# Sch.net
KiCad netlist of a schematic drawn in Altium Designer
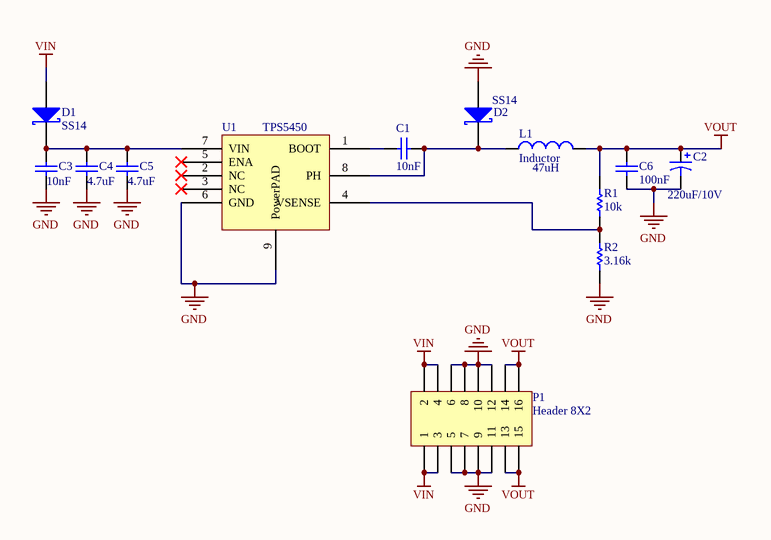
[diagram p0: Sch.SchDoc]

(export (version "E")
  (design (tool "Eeschema 10.0.6"))
  (components
    (comp (ref "C1")
      (value "10nF")
      (footprint "CAP1608(0603)")
      (description "Capacitor")
      (fields (field (name "PUBLISHER") "Altium Limited"))
      (libsource (lib "Miscellaneous Devices") (part "Cap"))
    )
    (comp (ref "C2")
      (value "220uF/10V")
      (footprint "CAP 2.5*6.3*7")
      (description "Polarized Capacitor (Radial)")
      (fields (field (name "PUBLISHER") "Altium Limited"))
      (libsource (lib "Miscellaneous Devices") (part "Cap Pol1"))
    )
    (comp (ref "C3")
      (value "10nF")
      (footprint "CAP1608(0603)")
      (description "Capacitor")
      (fields (field (name "PUBLISHER") "Altium Limited"))
      (libsource (lib "Miscellaneous Devices") (part "Cap"))
    )
    (comp (ref "C4")
      (value "4.7uF")
      (footprint "CAPC2012L")
      (description "Capacitor")
      (fields (field (name "PUBLISHER") "Altium Limited"))
      (libsource (lib "Miscellaneous Devices") (part "Cap"))
    )
    (comp (ref "C5")
      (value "4.7uF")
      (footprint "CAPC2012L")
      (description "Capacitor")
      (fields (field (name "PUBLISHER") "Altium Limited"))
      (libsource (lib "Miscellaneous Devices") (part "Cap"))
    )
    (comp (ref "C6")
      (value "100nF")
      (footprint "CAP1608(0603)")
      (description "Capacitor")
      (fields (field (name "PUBLISHER") "Altium Limited"))
      (libsource (lib "Miscellaneous Devices") (part "Cap"))
    )
    (comp (ref "D1")
      (value "SS14")
      (footprint "DIODE_SMA")
      (description "Schottky Diode")
      (fields (field (name "PUBLISHER") "Altium Limited"))
      (libsource (lib "Miscellaneous Devices") (part "D Schottky"))
    )
    (comp (ref "D2")
      (value "SS14")
      (footprint "DIODE_SMA")
      (description "Schottky Diode")
      (fields (field (name "PUBLISHER") "Altium Limited"))
      (libsource (lib "Miscellaneous Devices") (part "D Schottky"))
    )
    (comp (ref "L1")
      (value "Inductor")
      (footprint "CD43")
      (fields (field (name "ALTIUM_VALUE") "47uH") (field (name "PUBLISHER") "Altium Limited"))
      (libsource (lib "Miscellaneous Devices") (part "Inductor"))
    )
    (comp (ref "P1")
      (value "Header 8X2")
      (footprint "HDR2X8")
      (description "Header, 8-Pin, Dual row")
      (fields (field (name "PUBLISHER") "Altium Limited"))
      (libsource (lib "Miscellaneous Connectors") (part "Header 8X2"))
    )
    (comp (ref "R1")
      (value "10k")
      (footprint "RES1608(0603)")
      (description "Resistor")
      (fields (field (name "PUBLISHER") "Altium Limited"))
      (libsource (lib "Miscellaneous Devices") (part "Res1"))
    )
    (comp (ref "R2")
      (value "3.16k")
      (footprint "RES1608(0603)")
      (description "Resistor")
      (fields (field (name "PUBLISHER") "Altium Limited"))
      (libsource (lib "Miscellaneous Devices") (part "Res1"))
    )
    (comp (ref "U1") (value "TPS5450") (footprint "TPS5450") (libsource (lib "MySchlib") (part "TPS5450")))
  )
  (nets
    (net (code "1") (name "GND") (class "Default")
      (node (ref "C2") (pin "2") (pinfunction "2_2") (pintype "passive"))
      (node (ref "C3") (pin "2") (pinfunction "2_2") (pintype "passive"))
      (node (ref "C4") (pin "2") (pinfunction "2_2") (pintype "passive"))
      (node (ref "C5") (pin "2") (pinfunction "2_2") (pintype "passive"))
      (node (ref "C6") (pin "2") (pinfunction "2_2") (pintype "passive"))
      (node (ref "D2") (pin "1") (pinfunction "A_1") (pintype "passive"))
      (node (ref "P1") (pin "10") (pinfunction "10_10") (pintype "passive"))
      (node (ref "P1") (pin "11") (pinfunction "11_11") (pintype "passive"))
      (node (ref "P1") (pin "12") (pinfunction "12_12") (pintype "passive"))
      (node (ref "P1") (pin "5") (pinfunction "5_5") (pintype "passive"))
      (node (ref "P1") (pin "6") (pinfunction "6_6") (pintype "passive"))
      (node (ref "P1") (pin "7") (pinfunction "7_7") (pintype "passive"))
      (node (ref "P1") (pin "8") (pinfunction "8_8") (pintype "passive"))
      (node (ref "P1") (pin "9") (pinfunction "9_9") (pintype "passive"))
      (node (ref "R2") (pin "1") (pinfunction "1_1") (pintype "passive"))
      (node (ref "U1") (pin "6") (pinfunction "GND_6") (pintype "passive"))
      (node (ref "U1") (pin "9") (pinfunction "PowerPAD_9") (pintype "passive"))
    )
    (net (code "2") (name "Net-(D1-K)") (class "Default")
      (node (ref "C3") (pin "1") (pinfunction "1_1") (pintype "passive"))
      (node (ref "C4") (pin "1") (pinfunction "1_1") (pintype "passive"))
      (node (ref "C5") (pin "1") (pinfunction "1_1") (pintype "passive"))
      (node (ref "D1") (pin "2") (pinfunction "K_2") (pintype "passive"))
      (node (ref "U1") (pin "7") (pinfunction "VIN_7") (pintype "passive"))
    )
    (net (code "3") (name "Net-(D2-K)") (class "Default")
      (node (ref "C1") (pin "2") (pinfunction "2_2") (pintype "passive"))
      (node (ref "D2") (pin "2") (pinfunction "K_2") (pintype "passive"))
      (node (ref "L1") (pin "1") (pinfunction "1_1") (pintype "passive"))
      (node (ref "U1") (pin "8") (pinfunction "PH_8") (pintype "passive"))
    )
    (net (code "4") (name "Net-(U1-BOOT)") (class "Default")
      (node (ref "C1") (pin "1") (pinfunction "1_1") (pintype "passive"))
      (node (ref "U1") (pin "1") (pinfunction "BOOT_1") (pintype "passive"))
    )
    (net (code "5") (name "Net-(U1-VSENSE)") (class "Default")
      (node (ref "R1") (pin "1") (pinfunction "1_1") (pintype "passive"))
      (node (ref "R2") (pin "2") (pinfunction "2_2") (pintype "passive"))
      (node (ref "U1") (pin "4") (pinfunction "VSENSE_4") (pintype "passive"))
    )
    (net (code "6") (name "VIN") (class "Default")
      (node (ref "D1") (pin "1") (pinfunction "A_1") (pintype "passive"))
      (node (ref "P1") (pin "1") (pinfunction "1_1") (pintype "passive"))
      (node (ref "P1") (pin "2") (pinfunction "2_2") (pintype "passive"))
      (node (ref "P1") (pin "3") (pinfunction "3_3") (pintype "passive"))
      (node (ref "P1") (pin "4") (pinfunction "4_4") (pintype "passive"))
    )
    (net (code "7") (name "VOUT") (class "Default")
      (node (ref "C2") (pin "1") (pinfunction "1_1") (pintype "passive"))
      (node (ref "C6") (pin "1") (pinfunction "1_1") (pintype "passive"))
      (node (ref "L1") (pin "2") (pinfunction "2_2") (pintype "passive"))
      (node (ref "P1") (pin "13") (pinfunction "13_13") (pintype "passive"))
      (node (ref "P1") (pin "14") (pinfunction "14_14") (pintype "passive"))
      (node (ref "P1") (pin "15") (pinfunction "15_15") (pintype "passive"))
      (node (ref "P1") (pin "16") (pinfunction "16_16") (pintype "passive"))
      (node (ref "R1") (pin "2") (pinfunction "2_2") (pintype "passive"))
    )
    (net (code "8") (name "unconnected-(U1-ENA-Pad5)") (class "Default")
      (node (ref "U1") (pin "5") (pinfunction "ENA_5") (pintype "passive+no_connect"))
    )
    (net (code "9") (name "unconnected-(U1-NC-Pad2)") (class "Default")
      (node (ref "U1") (pin "2") (pinfunction "NC_2") (pintype "passive+no_connect"))
    )
    (net (code "10") (name "unconnected-(U1-NC-Pad3)") (class "Default")
      (node (ref "U1") (pin "3") (pinfunction "NC_3") (pintype "passive+no_connect"))
    )
  )
)
